# lcd.net
KiCad netlist of a schematic drawn in Altium Designer
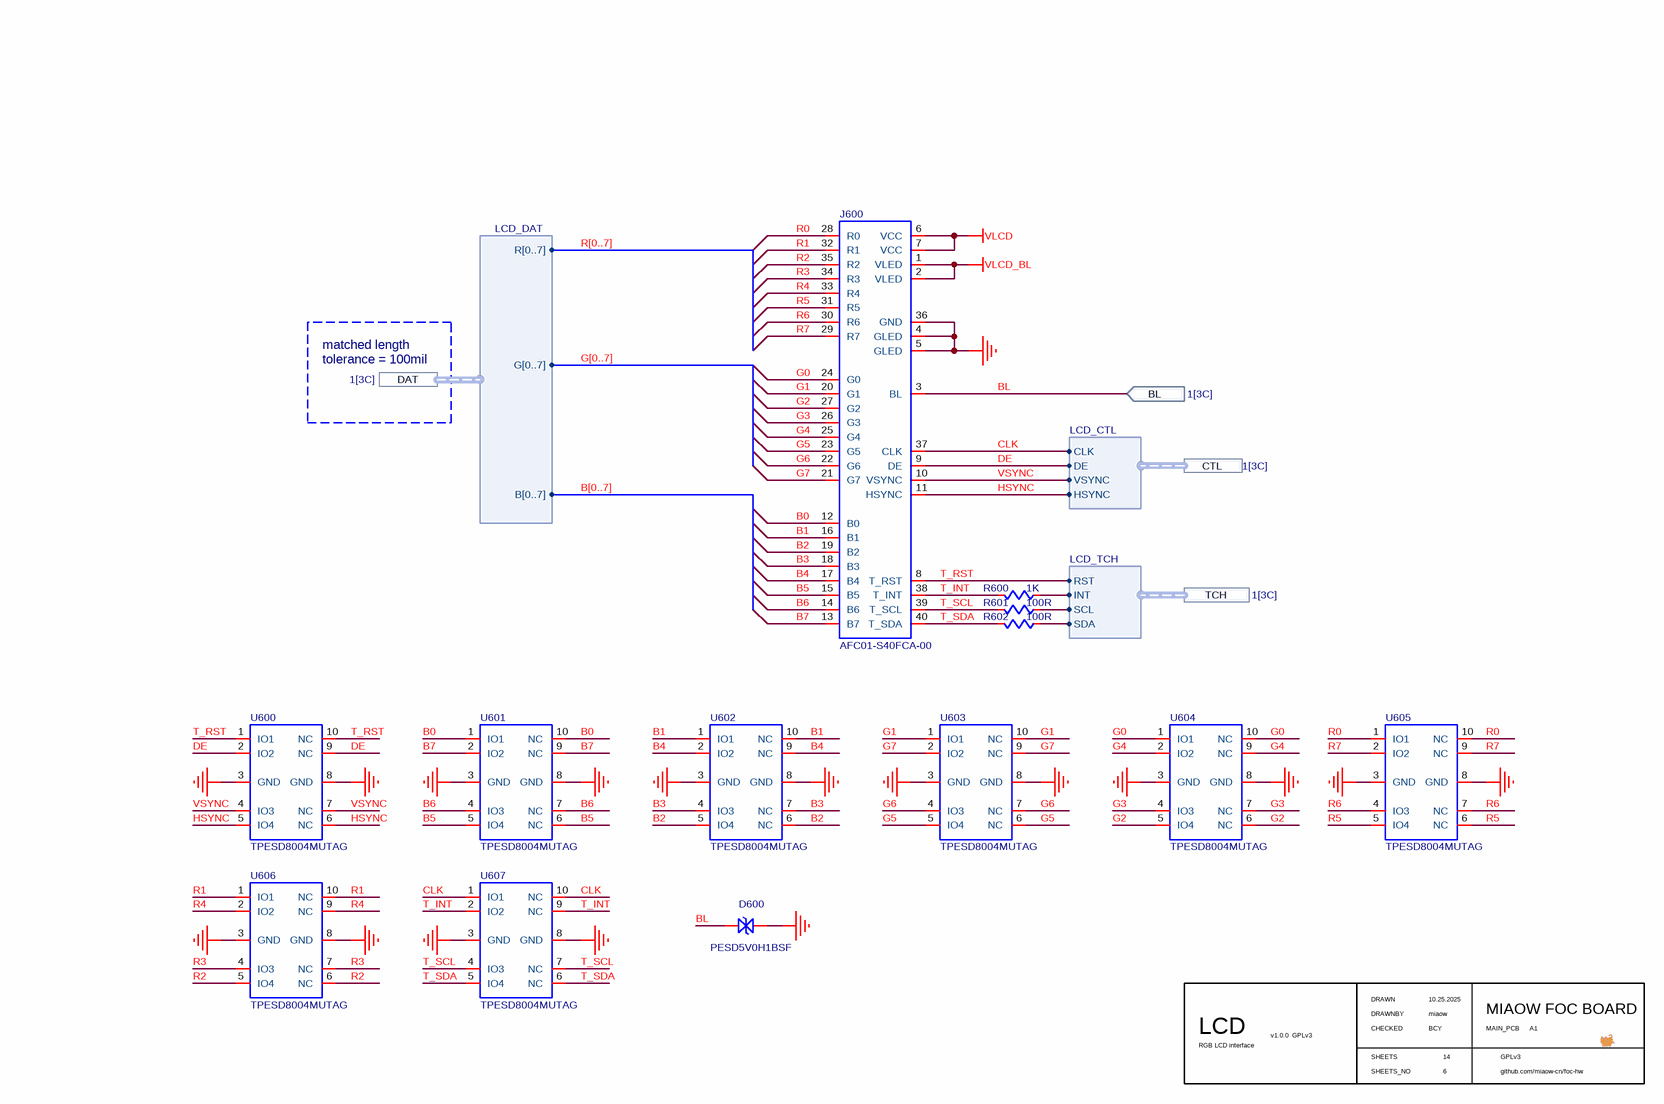
[diagram p0: lcd.schdoc]

(export (version "E")
  (design (tool "Eeschema 10.0.6"))
  (components
    (comp (ref "D600")
      (value "PESD5V0H1BSF")
      (footprint "mw:PESD5V0H1BSF")
      (description "TVS/ESD")
      (libsource (lib "mw") (part "PESD5V0H1BSF"))
    )
    (comp (ref "J600")
      (value "AFC01-S40FCA-00")
      (footprint "mw:AFC01-S40FCA-00")
      (libsource (lib "mw") (part "FPC-RGBLCD"))
    )
    (comp (ref "R600")
      (value "1K")
      (footprint "mw:R0402")
      (fields (field (name "Comment") "R"))
      (libsource (lib "mw") (part "R"))
    )
    (comp (ref "R601")
      (value "100R")
      (footprint "mw:R0402")
      (fields (field (name "Comment") "R"))
      (libsource (lib "mw") (part "R"))
    )
    (comp (ref "R602")
      (value "100R")
      (footprint "mw:R0402")
      (fields (field (name "Comment") "R"))
      (libsource (lib "mw") (part "R"))
    )
    (comp (ref "U600")
      (value "TPESD8004MUTAG")
      (footprint "mw:TPESD8004MUTAG")
      (description "TVS/ESD")
      (libsource (lib "mw") (part "TPESD8004MUTAG"))
    )
    (comp (ref "U601")
      (value "TPESD8004MUTAG")
      (footprint "mw:TPESD8004MUTAG")
      (description "TVS/ESD")
      (libsource (lib "mw") (part "TPESD8004MUTAG"))
    )
    (comp (ref "U602")
      (value "TPESD8004MUTAG")
      (footprint "mw:TPESD8004MUTAG")
      (description "TVS/ESD")
      (libsource (lib "mw") (part "TPESD8004MUTAG"))
    )
    (comp (ref "U603")
      (value "TPESD8004MUTAG")
      (footprint "mw:TPESD8004MUTAG")
      (description "TVS/ESD")
      (libsource (lib "mw") (part "TPESD8004MUTAG"))
    )
    (comp (ref "U604")
      (value "TPESD8004MUTAG")
      (footprint "mw:TPESD8004MUTAG")
      (description "TVS/ESD")
      (libsource (lib "mw") (part "TPESD8004MUTAG"))
    )
    (comp (ref "U605")
      (value "TPESD8004MUTAG")
      (footprint "mw:TPESD8004MUTAG")
      (description "TVS/ESD")
      (libsource (lib "mw") (part "TPESD8004MUTAG"))
    )
    (comp (ref "U606")
      (value "TPESD8004MUTAG")
      (footprint "mw:TPESD8004MUTAG")
      (description "TVS/ESD")
      (libsource (lib "mw") (part "TPESD8004MUTAG"))
    )
    (comp (ref "U607")
      (value "TPESD8004MUTAG")
      (footprint "mw:TPESD8004MUTAG")
      (description "TVS/ESD")
      (libsource (lib "mw") (part "TPESD8004MUTAG"))
    )
  )
  (nets
    (net (code "3") (name "/B0") (class "Default")
      (node (ref "J600") (pin "12") (pinfunction "B0_12") (pintype "passive"))
      (node (ref "U601") (pin "1") (pinfunction "IO1_1") (pintype "passive"))
      (node (ref "U601") (pin "10") (pinfunction "NC_10") (pintype "passive"))
    )
    (net (code "4") (name "/B1") (class "Default")
      (node (ref "J600") (pin "16") (pinfunction "B1_16") (pintype "passive"))
      (node (ref "U602") (pin "1") (pinfunction "IO1_1") (pintype "passive"))
      (node (ref "U602") (pin "10") (pinfunction "NC_10") (pintype "passive"))
    )
    (net (code "5") (name "/B2") (class "Default")
      (node (ref "J600") (pin "19") (pinfunction "B2_19") (pintype "passive"))
      (node (ref "U602") (pin "5") (pinfunction "IO4_5") (pintype "passive"))
      (node (ref "U602") (pin "6") (pinfunction "NC_6") (pintype "passive"))
    )
    (net (code "6") (name "/B3") (class "Default")
      (node (ref "J600") (pin "18") (pinfunction "B3_18") (pintype "passive"))
      (node (ref "U602") (pin "4") (pinfunction "IO3_4") (pintype "passive"))
      (node (ref "U602") (pin "7") (pinfunction "NC_7") (pintype "passive"))
    )
    (net (code "7") (name "/B4") (class "Default")
      (node (ref "J600") (pin "17") (pinfunction "B4_17") (pintype "passive"))
      (node (ref "U602") (pin "2") (pinfunction "IO2_2") (pintype "passive"))
      (node (ref "U602") (pin "9") (pinfunction "NC_9") (pintype "passive"))
    )
    (net (code "8") (name "/B5") (class "Default")
      (node (ref "J600") (pin "15") (pinfunction "B5_15") (pintype "passive"))
      (node (ref "U601") (pin "5") (pinfunction "IO4_5") (pintype "passive"))
      (node (ref "U601") (pin "6") (pinfunction "NC_6") (pintype "passive"))
    )
    (net (code "9") (name "/B6") (class "Default")
      (node (ref "J600") (pin "14") (pinfunction "B6_14") (pintype "passive"))
      (node (ref "U601") (pin "4") (pinfunction "IO3_4") (pintype "passive"))
      (node (ref "U601") (pin "7") (pinfunction "NC_7") (pintype "passive"))
    )
    (net (code "10") (name "/B7") (class "Default")
      (node (ref "J600") (pin "13") (pinfunction "B7_13") (pintype "passive"))
      (node (ref "U601") (pin "2") (pinfunction "IO2_2") (pintype "passive"))
      (node (ref "U601") (pin "9") (pinfunction "NC_9") (pintype "passive"))
    )
    (net (code "11") (name "/BL") (class "Default")
      (node (ref "D600") (pin "1") (pinfunction "1_1") (pintype "passive"))
      (node (ref "J600") (pin "3") (pinfunction "BL_3") (pintype "passive"))
    )
    (net (code "13") (name "/CLK") (class "Default")
      (node (ref "J600") (pin "37") (pinfunction "CLK_37") (pintype "passive"))
      (node (ref "U607") (pin "1") (pinfunction "IO1_1") (pintype "passive"))
      (node (ref "U607") (pin "10") (pinfunction "NC_10") (pintype "passive"))
    )
    (net (code "14") (name "/DE") (class "Default")
      (node (ref "J600") (pin "9") (pinfunction "DE_9") (pintype "passive"))
      (node (ref "U600") (pin "2") (pinfunction "IO2_2") (pintype "passive"))
      (node (ref "U600") (pin "9") (pinfunction "NC_9") (pintype "passive"))
    )
    (net (code "15") (name "/G0") (class "Default")
      (node (ref "J600") (pin "24") (pinfunction "G0_24") (pintype "passive"))
      (node (ref "U604") (pin "1") (pinfunction "IO1_1") (pintype "passive"))
      (node (ref "U604") (pin "10") (pinfunction "NC_10") (pintype "passive"))
    )
    (net (code "16") (name "/G1") (class "Default")
      (node (ref "J600") (pin "20") (pinfunction "G1_20") (pintype "passive"))
      (node (ref "U603") (pin "1") (pinfunction "IO1_1") (pintype "passive"))
      (node (ref "U603") (pin "10") (pinfunction "NC_10") (pintype "passive"))
    )
    (net (code "17") (name "/G2") (class "Default")
      (node (ref "J600") (pin "27") (pinfunction "G2_27") (pintype "passive"))
      (node (ref "U604") (pin "5") (pinfunction "IO4_5") (pintype "passive"))
      (node (ref "U604") (pin "6") (pinfunction "NC_6") (pintype "passive"))
    )
    (net (code "18") (name "/G3") (class "Default")
      (node (ref "J600") (pin "26") (pinfunction "G3_26") (pintype "passive"))
      (node (ref "U604") (pin "4") (pinfunction "IO3_4") (pintype "passive"))
      (node (ref "U604") (pin "7") (pinfunction "NC_7") (pintype "passive"))
    )
    (net (code "19") (name "/G4") (class "Default")
      (node (ref "J600") (pin "25") (pinfunction "G4_25") (pintype "passive"))
      (node (ref "U604") (pin "2") (pinfunction "IO2_2") (pintype "passive"))
      (node (ref "U604") (pin "9") (pinfunction "NC_9") (pintype "passive"))
    )
    (net (code "20") (name "/G5") (class "Default")
      (node (ref "J600") (pin "23") (pinfunction "G5_23") (pintype "passive"))
      (node (ref "U603") (pin "5") (pinfunction "IO4_5") (pintype "passive"))
      (node (ref "U603") (pin "6") (pinfunction "NC_6") (pintype "passive"))
    )
    (net (code "21") (name "/G6") (class "Default")
      (node (ref "J600") (pin "22") (pinfunction "G6_22") (pintype "passive"))
      (node (ref "U603") (pin "4") (pinfunction "IO3_4") (pintype "passive"))
      (node (ref "U603") (pin "7") (pinfunction "NC_7") (pintype "passive"))
    )
    (net (code "22") (name "/G7") (class "Default")
      (node (ref "J600") (pin "21") (pinfunction "G7_21") (pintype "passive"))
      (node (ref "U603") (pin "2") (pinfunction "IO2_2") (pintype "passive"))
      (node (ref "U603") (pin "9") (pinfunction "NC_9") (pintype "passive"))
    )
    (net (code "24") (name "/HSYNC") (class "Default")
      (node (ref "J600") (pin "11") (pinfunction "HSYNC_11") (pintype "passive"))
      (node (ref "U600") (pin "5") (pinfunction "IO4_5") (pintype "passive"))
      (node (ref "U600") (pin "6") (pinfunction "NC_6") (pintype "passive"))
    )
    (net (code "25") (name "/INT") (class "Default")
      (node (ref "R600") (pin "2") (pinfunction "2_2") (pintype "passive"))
    )
    (net (code "26") (name "/R0") (class "Default")
      (node (ref "J600") (pin "28") (pinfunction "R0_28") (pintype "passive"))
      (node (ref "U605") (pin "1") (pinfunction "IO1_1") (pintype "passive"))
      (node (ref "U605") (pin "10") (pinfunction "NC_10") (pintype "passive"))
    )
    (net (code "27") (name "/R1") (class "Default")
      (node (ref "J600") (pin "32") (pinfunction "R1_32") (pintype "passive"))
      (node (ref "U606") (pin "1") (pinfunction "IO1_1") (pintype "passive"))
      (node (ref "U606") (pin "10") (pinfunction "NC_10") (pintype "passive"))
    )
    (net (code "28") (name "/R2") (class "Default")
      (node (ref "J600") (pin "35") (pinfunction "R2_35") (pintype "passive"))
      (node (ref "U606") (pin "5") (pinfunction "IO4_5") (pintype "passive"))
      (node (ref "U606") (pin "6") (pinfunction "NC_6") (pintype "passive"))
    )
    (net (code "29") (name "/R3") (class "Default")
      (node (ref "J600") (pin "34") (pinfunction "R3_34") (pintype "passive"))
      (node (ref "U606") (pin "4") (pinfunction "IO3_4") (pintype "passive"))
      (node (ref "U606") (pin "7") (pinfunction "NC_7") (pintype "passive"))
    )
    (net (code "30") (name "/R4") (class "Default")
      (node (ref "J600") (pin "33") (pinfunction "R4_33") (pintype "passive"))
      (node (ref "U606") (pin "2") (pinfunction "IO2_2") (pintype "passive"))
      (node (ref "U606") (pin "9") (pinfunction "NC_9") (pintype "passive"))
    )
    (net (code "31") (name "/R5") (class "Default")
      (node (ref "J600") (pin "31") (pinfunction "R5_31") (pintype "passive"))
      (node (ref "U605") (pin "5") (pinfunction "IO4_5") (pintype "passive"))
      (node (ref "U605") (pin "6") (pinfunction "NC_6") (pintype "passive"))
    )
    (net (code "32") (name "/R6") (class "Default")
      (node (ref "J600") (pin "30") (pinfunction "R6_30") (pintype "passive"))
      (node (ref "U605") (pin "4") (pinfunction "IO3_4") (pintype "passive"))
      (node (ref "U605") (pin "7") (pinfunction "NC_7") (pintype "passive"))
    )
    (net (code "33") (name "/R7") (class "Default")
      (node (ref "J600") (pin "29") (pinfunction "R7_29") (pintype "passive"))
      (node (ref "U605") (pin "2") (pinfunction "IO2_2") (pintype "passive"))
      (node (ref "U605") (pin "9") (pinfunction "NC_9") (pintype "passive"))
    )
    (net (code "34") (name "/SCL") (class "Default")
      (node (ref "R601") (pin "2") (pinfunction "2_2") (pintype "passive"))
    )
    (net (code "35") (name "/SDA") (class "Default")
      (node (ref "R602") (pin "2") (pinfunction "2_2") (pintype "passive"))
    )
    (net (code "36") (name "/T_INT") (class "Default")
      (node (ref "J600") (pin "38") (pinfunction "T_INT_38") (pintype "passive"))
      (node (ref "R600") (pin "1") (pinfunction "1_1") (pintype "passive"))
      (node (ref "U607") (pin "2") (pinfunction "IO2_2") (pintype "passive"))
      (node (ref "U607") (pin "9") (pinfunction "NC_9") (pintype "passive"))
    )
    (net (code "37") (name "/T_RST") (class "Default")
      (node (ref "J600") (pin "8") (pinfunction "T_RST_8") (pintype "passive"))
      (node (ref "U600") (pin "1") (pinfunction "IO1_1") (pintype "passive"))
      (node (ref "U600") (pin "10") (pinfunction "NC_10") (pintype "passive"))
    )
    (net (code "38") (name "/T_SCL") (class "Default")
      (node (ref "J600") (pin "39") (pinfunction "T_SCL_39") (pintype "passive"))
      (node (ref "R601") (pin "1") (pinfunction "1_1") (pintype "passive"))
      (node (ref "U607") (pin "4") (pinfunction "IO3_4") (pintype "passive"))
      (node (ref "U607") (pin "7") (pinfunction "NC_7") (pintype "passive"))
    )
    (net (code "39") (name "/T_SDA") (class "Default")
      (node (ref "J600") (pin "40") (pinfunction "T_SDA_40") (pintype "passive"))
      (node (ref "R602") (pin "1") (pinfunction "1_1") (pintype "passive"))
      (node (ref "U607") (pin "5") (pinfunction "IO4_5") (pintype "passive"))
      (node (ref "U607") (pin "6") (pinfunction "NC_6") (pintype "passive"))
    )
    (net (code "40") (name "/VSYNC") (class "Default")
      (node (ref "J600") (pin "10") (pinfunction "VSYNC_10") (pintype "passive"))
      (node (ref "U600") (pin "4") (pinfunction "IO3_4") (pintype "passive"))
      (node (ref "U600") (pin "7") (pinfunction "NC_7") (pintype "passive"))
    )
    (net (code "44") (name "GND") (class "Default")
      (node (ref "D600") (pin "2") (pinfunction "2_2") (pintype "passive"))
      (node (ref "J600") (pin "36") (pinfunction "GND_36") (pintype "passive"))
      (node (ref "J600") (pin "4") (pinfunction "GLED_4") (pintype "passive"))
      (node (ref "J600") (pin "5") (pinfunction "GLED_5") (pintype "passive"))
      (node (ref "U600") (pin "3") (pinfunction "GND_3") (pintype "passive"))
      (node (ref "U600") (pin "8") (pinfunction "GND_8") (pintype "passive"))
      (node (ref "U601") (pin "3") (pinfunction "GND_3") (pintype "passive"))
      (node (ref "U601") (pin "8") (pinfunction "GND_8") (pintype "passive"))
      (node (ref "U602") (pin "3") (pinfunction "GND_3") (pintype "passive"))
      (node (ref "U602") (pin "8") (pinfunction "GND_8") (pintype "passive"))
      (node (ref "U603") (pin "3") (pinfunction "GND_3") (pintype "passive"))
      (node (ref "U603") (pin "8") (pinfunction "GND_8") (pintype "passive"))
      (node (ref "U604") (pin "3") (pinfunction "GND_3") (pintype "passive"))
      (node (ref "U604") (pin "8") (pinfunction "GND_8") (pintype "passive"))
      (node (ref "U605") (pin "3") (pinfunction "GND_3") (pintype "passive"))
      (node (ref "U605") (pin "8") (pinfunction "GND_8") (pintype "passive"))
      (node (ref "U606") (pin "3") (pinfunction "GND_3") (pintype "passive"))
      (node (ref "U606") (pin "8") (pinfunction "GND_8") (pintype "passive"))
      (node (ref "U607") (pin "3") (pinfunction "GND_3") (pintype "passive"))
      (node (ref "U607") (pin "8") (pinfunction "GND_8") (pintype "passive"))
    )
    (net (code "45") (name "VLCD") (class "Default")
      (node (ref "J600") (pin "6") (pinfunction "VCC_6") (pintype "passive"))
      (node (ref "J600") (pin "7") (pinfunction "VCC_7") (pintype "passive"))
    )
    (net (code "46") (name "VLCD_BL") (class "Default")
      (node (ref "J600") (pin "1") (pinfunction "VLED_1") (pintype "passive"))
      (node (ref "J600") (pin "2") (pinfunction "VLED_2") (pintype "passive"))
    )
  )
)
